# BLE_--_HM-10_--_Breakout_v_9_2.net
KiCad netlist of a schematic drawn in EAGLE
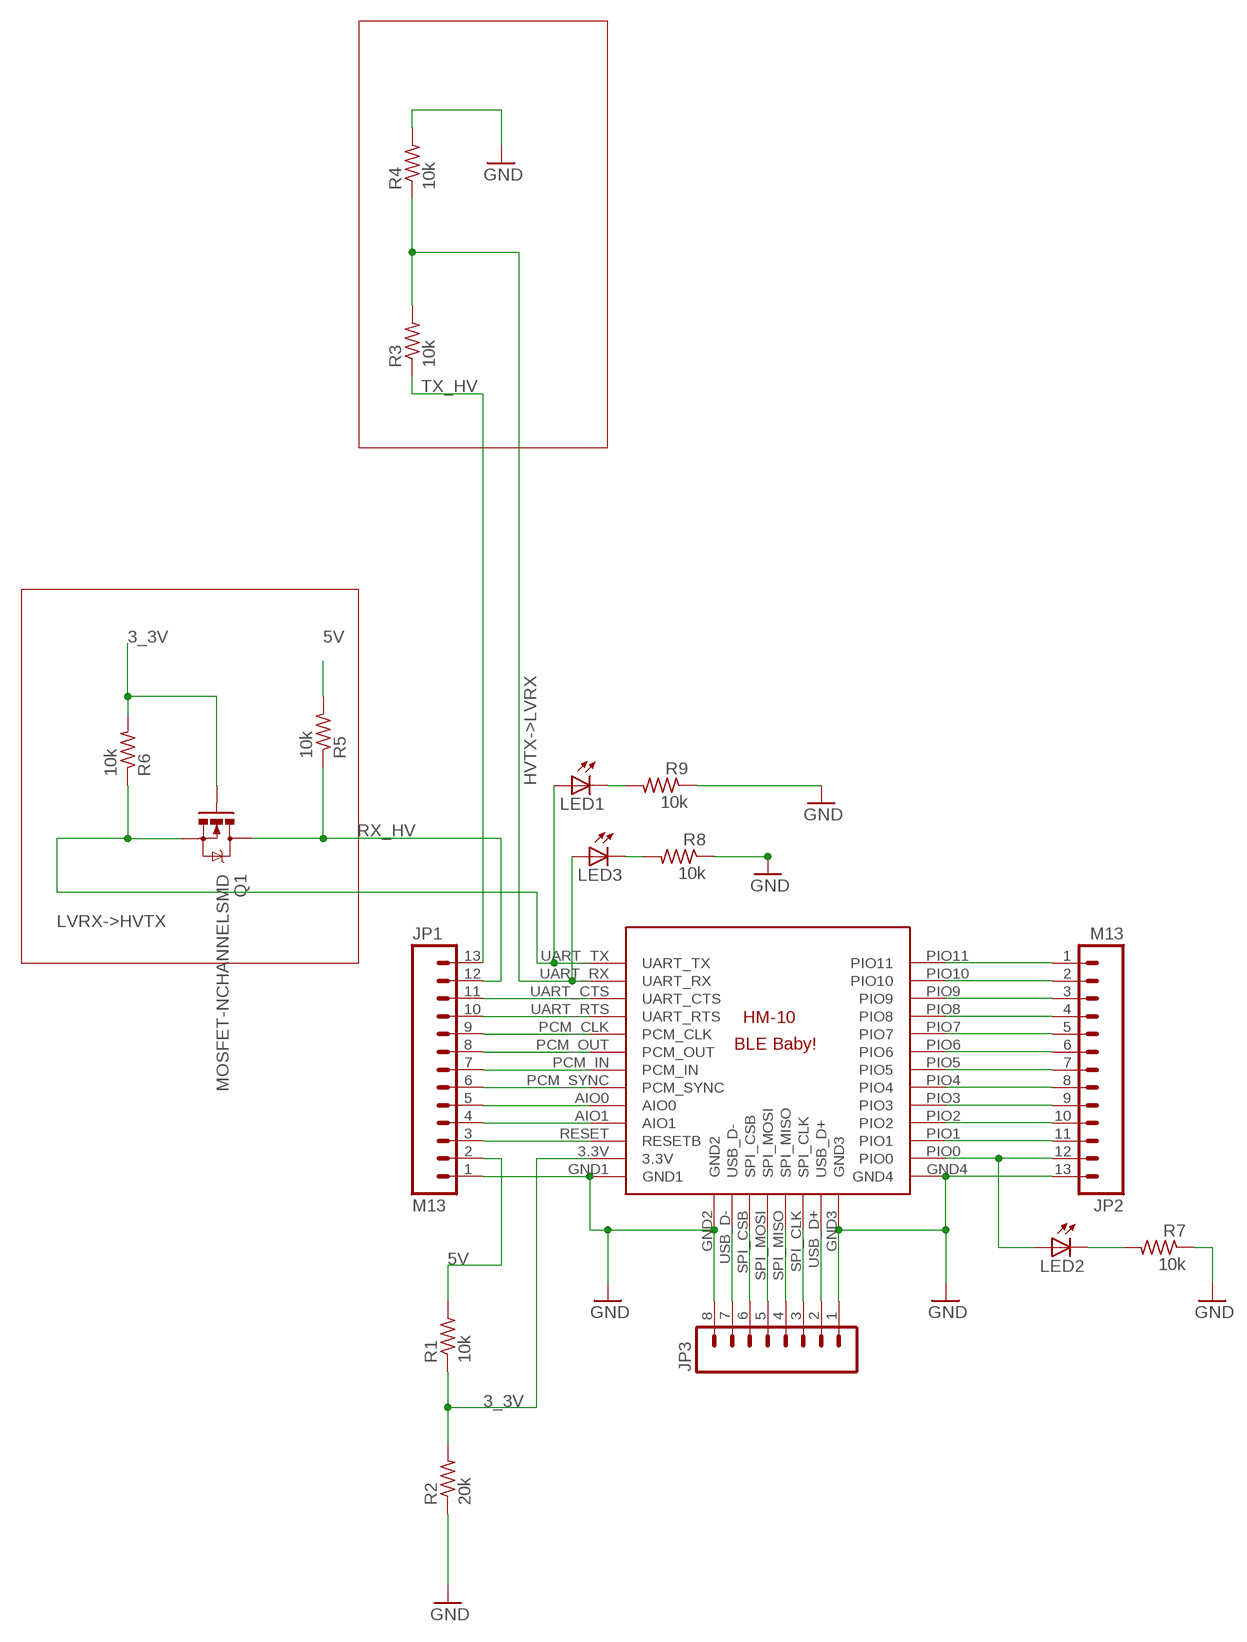
[diagram p0: schematic, sheet 1]

(export (version "E")
  (design (tool "Eeschema 10.0.6"))
  (components
    (comp (ref "JP1")
      (value "M13")
      (footprint "eagle-import:1X13")
      (libsource (lib "eagle-import") (part "M13"))
    )
    (comp (ref "JP2")
      (value "M13")
      (footprint "eagle-import:1X13")
      (libsource (lib "eagle-import") (part "M13"))
    )
    (comp (ref "JP3")
      (value "M081X08")
      (footprint "eagle-import:1X08")
      (libsource (lib "eagle-import") (part "M081X08"))
    )
    (comp (ref "LED1")
      (value "LED0603")
      (footprint "eagle-import:LED-0603")
      (libsource (lib "eagle-import") (part "LED0603"))
    )
    (comp (ref "LED2")
      (value "LED0603")
      (footprint "eagle-import:LED-0603")
      (libsource (lib "eagle-import") (part "LED0603"))
    )
    (comp (ref "LED3")
      (value "LED0603")
      (footprint "eagle-import:LED-0603")
      (libsource (lib "eagle-import") (part "LED0603"))
    )
    (comp (ref "Q1")
      (value "MOSFET-NCHANNELSMD")
      (footprint "eagle-import:SOT23-3")
      (libsource (lib "eagle-import") (part "MOSFET-NCHANNELSMD"))
    )
    (comp (ref "R1")
      (value "10k")
      (footprint "eagle-import:M0805")
      (libsource (lib "eagle-import") (part "R-US_M0805"))
    )
    (comp (ref "R2")
      (value "20k")
      (footprint "eagle-import:M0805")
      (libsource (lib "eagle-import") (part "R-US_M0805"))
    )
    (comp (ref "R3")
      (value "10k")
      (footprint "eagle-import:M0805")
      (libsource (lib "eagle-import") (part "R-US_M0805"))
    )
    (comp (ref "R4")
      (value "10k")
      (footprint "eagle-import:M0805")
      (libsource (lib "eagle-import") (part "R-US_M0805"))
    )
    (comp (ref "R5")
      (value "10k")
      (footprint "eagle-import:M0805")
      (libsource (lib "eagle-import") (part "R-US_M0805"))
    )
    (comp (ref "R6")
      (value "10k")
      (footprint "eagle-import:M0805")
      (libsource (lib "eagle-import") (part "R-US_M0805"))
    )
    (comp (ref "R7")
      (value "10k")
      (footprint "eagle-import:M0805")
      (libsource (lib "eagle-import") (part "R-US_M0805"))
    )
    (comp (ref "R8")
      (value "10k")
      (footprint "eagle-import:M0805")
      (libsource (lib "eagle-import") (part "R-US_M0805"))
    )
    (comp (ref "R9")
      (value "10k")
      (footprint "eagle-import:M0805")
      (libsource (lib "eagle-import") (part "R-US_M0805"))
    )
    (comp (ref "U$1")
      (value "BLE-HM-10")
      (footprint "eagle-import:BLE-HM-10")
      (libsource (lib "eagle-import") (part "BLE-HM-10"))
    )
  )
  (nets
    (net (code "1") (name "/3_3V") (class "Default")
      (node (ref "Q1") (pin "1") (pinfunction "G_1") (pintype "passive"))
      (node (ref "R1") (pin "1") (pinfunction "1_1") (pintype "passive"))
      (node (ref "R2") (pin "2") (pinfunction "2_2") (pintype "passive"))
      (node (ref "R6") (pin "2") (pinfunction "2_2") (pintype "passive"))
      (node (ref "U$1") (pin "3.3V") (pinfunction "3.3V_3.3V") (pintype "bidirectional"))
    )
    (net (code "2") (name "/5V") (class "Default")
      (node (ref "JP1") (pin "2") (pinfunction "2_2") (pintype "passive"))
      (node (ref "R1") (pin "2") (pinfunction "2_2") (pintype "passive"))
      (node (ref "R5") (pin "2") (pinfunction "2_2") (pintype "passive"))
    )
    (net (code "3") (name "/HVTX->LVRX") (class "Default")
      (node (ref "LED3") (pin "A") (pinfunction "A_A") (pintype "passive"))
      (node (ref "R3") (pin "2") (pinfunction "2_2") (pintype "passive"))
      (node (ref "R4") (pin "1") (pinfunction "1_1") (pintype "passive"))
      (node (ref "U$1") (pin "UART_RX") (pinfunction "UART_RX_UART_RX") (pintype "bidirectional"))
    )
    (net (code "4") (name "/LVRX->HVTX") (class "Default")
      (node (ref "LED1") (pin "A") (pinfunction "A_A") (pintype "passive"))
      (node (ref "Q1") (pin "2") (pinfunction "S_2") (pintype "passive"))
      (node (ref "R6") (pin "1") (pinfunction "1_1") (pintype "passive"))
      (node (ref "U$1") (pin "UART_TX") (pinfunction "UART_TX_UART_TX") (pintype "bidirectional"))
    )
    (net (code "5") (name "/RX_HV") (class "Default")
      (node (ref "JP1") (pin "12") (pinfunction "12_12") (pintype "passive"))
      (node (ref "Q1") (pin "3") (pinfunction "D_3") (pintype "passive"))
      (node (ref "R5") (pin "1") (pinfunction "1_1") (pintype "passive"))
    )
    (net (code "6") (name "/TX_HV") (class "Default")
      (node (ref "JP1") (pin "13") (pinfunction "13_13") (pintype "passive"))
      (node (ref "R3") (pin "1") (pinfunction "1_1") (pintype "passive"))
    )
    (net (code "7") (name "GND") (class "Default")
      (node (ref "JP1") (pin "1") (pinfunction "1_1") (pintype "passive"))
      (node (ref "JP2") (pin "13") (pinfunction "13_13") (pintype "passive"))
      (node (ref "JP3") (pin "1") (pinfunction "1_1") (pintype "passive"))
      (node (ref "JP3") (pin "8") (pinfunction "8_8") (pintype "passive"))
      (node (ref "R2") (pin "1") (pinfunction "1_1") (pintype "passive"))
      (node (ref "R4") (pin "2") (pinfunction "2_2") (pintype "passive"))
      (node (ref "R7") (pin "1") (pinfunction "1_1") (pintype "passive"))
      (node (ref "R8") (pin "1") (pinfunction "1_1") (pintype "passive"))
      (node (ref "R9") (pin "1") (pinfunction "1_1") (pintype "passive"))
      (node (ref "U$1") (pin "GND1") (pinfunction "GND1_GND1") (pintype "bidirectional"))
      (node (ref "U$1") (pin "GND2") (pinfunction "GND2_GND2") (pintype "bidirectional"))
      (node (ref "U$1") (pin "GND3") (pinfunction "GND3_GND3") (pintype "bidirectional"))
      (node (ref "U$1") (pin "GND4") (pinfunction "GND4_GND4") (pintype "bidirectional"))
    )
    (net (code "8") (name "Net-(JP1-Pad4)") (class "Default")
      (node (ref "JP1") (pin "4") (pinfunction "4_4") (pintype "passive"))
      (node (ref "U$1") (pin "AIO1") (pinfunction "AIO1_AIO1") (pintype "bidirectional"))
    )
    (net (code "9") (name "Net-(JP1-Pad5)") (class "Default")
      (node (ref "JP1") (pin "5") (pinfunction "5_5") (pintype "passive"))
      (node (ref "U$1") (pin "AIO0") (pinfunction "AIO0_AIO0") (pintype "bidirectional"))
    )
    (net (code "10") (name "Net-(JP1-Pad6)") (class "Default")
      (node (ref "JP1") (pin "6") (pinfunction "6_6") (pintype "passive"))
      (node (ref "U$1") (pin "PCM_SYNC") (pinfunction "PCM_SYNC_PCM_SYNC") (pintype "bidirectional"))
    )
    (net (code "11") (name "Net-(JP1-Pad7)") (class "Default")
      (node (ref "JP1") (pin "7") (pinfunction "7_7") (pintype "passive"))
      (node (ref "U$1") (pin "PCM_IN") (pinfunction "PCM_IN_PCM_IN") (pintype "bidirectional"))
    )
    (net (code "12") (name "Net-(JP1-Pad8)") (class "Default")
      (node (ref "JP1") (pin "8") (pinfunction "8_8") (pintype "passive"))
      (node (ref "U$1") (pin "PCM_OUT") (pinfunction "PCM_OUT_PCM_OUT") (pintype "bidirectional"))
    )
    (net (code "13") (name "Net-(JP1-Pad9)") (class "Default")
      (node (ref "JP1") (pin "9") (pinfunction "9_9") (pintype "passive"))
      (node (ref "U$1") (pin "PCM_CLK") (pinfunction "PCM_CLK_PCM_CLK") (pintype "bidirectional"))
    )
    (net (code "14") (name "Net-(JP1-Pad10)") (class "Default")
      (node (ref "JP1") (pin "10") (pinfunction "10_10") (pintype "passive"))
      (node (ref "U$1") (pin "UART_RTS") (pinfunction "UART_RTS_UART_RTS") (pintype "bidirectional"))
    )
    (net (code "15") (name "Net-(JP1-Pad11)") (class "Default")
      (node (ref "JP1") (pin "11") (pinfunction "11_11") (pintype "passive"))
      (node (ref "U$1") (pin "UART_CTS") (pinfunction "UART_CTS_UART_CTS") (pintype "bidirectional"))
    )
    (net (code "16") (name "Net-(JP2-Pad1)") (class "Default")
      (node (ref "JP2") (pin "1") (pinfunction "1_1") (pintype "passive"))
      (node (ref "U$1") (pin "PIO11") (pinfunction "PIO11_PIO11") (pintype "bidirectional"))
    )
    (net (code "17") (name "Net-(JP2-Pad2)") (class "Default")
      (node (ref "JP2") (pin "2") (pinfunction "2_2") (pintype "passive"))
      (node (ref "U$1") (pin "PIO10") (pinfunction "PIO10_PIO10") (pintype "bidirectional"))
    )
    (net (code "18") (name "Net-(JP2-Pad3)") (class "Default")
      (node (ref "JP2") (pin "3") (pinfunction "3_3") (pintype "passive"))
      (node (ref "U$1") (pin "PIO9") (pinfunction "PIO9_PIO9") (pintype "bidirectional"))
    )
    (net (code "19") (name "Net-(JP2-Pad4)") (class "Default")
      (node (ref "JP2") (pin "4") (pinfunction "4_4") (pintype "passive"))
      (node (ref "U$1") (pin "PIO8") (pinfunction "PIO8_PIO8") (pintype "bidirectional"))
    )
    (net (code "20") (name "Net-(JP2-Pad5)") (class "Default")
      (node (ref "JP2") (pin "5") (pinfunction "5_5") (pintype "passive"))
      (node (ref "U$1") (pin "PIO7") (pinfunction "PIO7_PIO7") (pintype "bidirectional"))
    )
    (net (code "21") (name "Net-(JP2-Pad6)") (class "Default")
      (node (ref "JP2") (pin "6") (pinfunction "6_6") (pintype "passive"))
      (node (ref "U$1") (pin "PIO6") (pinfunction "PIO6_PIO6") (pintype "bidirectional"))
    )
    (net (code "22") (name "Net-(JP2-Pad7)") (class "Default")
      (node (ref "JP2") (pin "7") (pinfunction "7_7") (pintype "passive"))
      (node (ref "U$1") (pin "PIO5") (pinfunction "PIO5_PIO5") (pintype "bidirectional"))
    )
    (net (code "23") (name "Net-(JP2-Pad8)") (class "Default")
      (node (ref "JP2") (pin "8") (pinfunction "8_8") (pintype "passive"))
      (node (ref "U$1") (pin "PIO4") (pinfunction "PIO4_PIO4") (pintype "bidirectional"))
    )
    (net (code "24") (name "Net-(JP2-Pad9)") (class "Default")
      (node (ref "JP2") (pin "9") (pinfunction "9_9") (pintype "passive"))
      (node (ref "U$1") (pin "PIO3") (pinfunction "PIO3_PIO3") (pintype "bidirectional"))
    )
    (net (code "25") (name "Net-(JP2-Pad10)") (class "Default")
      (node (ref "JP2") (pin "10") (pinfunction "10_10") (pintype "passive"))
      (node (ref "U$1") (pin "PIO2") (pinfunction "PIO2_PIO2") (pintype "bidirectional"))
    )
    (net (code "26") (name "Net-(JP2-Pad11)") (class "Default")
      (node (ref "JP2") (pin "11") (pinfunction "11_11") (pintype "passive"))
      (node (ref "U$1") (pin "PIO1") (pinfunction "PIO1_PIO1") (pintype "bidirectional"))
    )
    (net (code "27") (name "Net-(JP2-Pad12)") (class "Default")
      (node (ref "JP2") (pin "12") (pinfunction "12_12") (pintype "passive"))
      (node (ref "LED2") (pin "A") (pinfunction "A_A") (pintype "passive"))
      (node (ref "U$1") (pin "PIO0") (pinfunction "PIO0_PIO0") (pintype "bidirectional"))
    )
    (net (code "28") (name "Net-(JP3-Pad2)") (class "Default")
      (node (ref "JP3") (pin "2") (pinfunction "2_2") (pintype "passive"))
      (node (ref "U$1") (pin "USB_D+") (pinfunction "USB_D+_USB_D+") (pintype "bidirectional"))
    )
    (net (code "29") (name "Net-(JP3-Pad3)") (class "Default")
      (node (ref "JP3") (pin "3") (pinfunction "3_3") (pintype "passive"))
      (node (ref "U$1") (pin "SPI_CLK") (pinfunction "SPI_CLK_SPI_CLK") (pintype "bidirectional"))
    )
    (net (code "30") (name "Net-(JP3-Pad4)") (class "Default")
      (node (ref "JP3") (pin "4") (pinfunction "4_4") (pintype "passive"))
      (node (ref "U$1") (pin "SPI_MISO") (pinfunction "SPI_MISO_SPI_MISO") (pintype "bidirectional"))
    )
    (net (code "31") (name "Net-(JP3-Pad5)") (class "Default")
      (node (ref "JP3") (pin "5") (pinfunction "5_5") (pintype "passive"))
      (node (ref "U$1") (pin "SPI_MOSI") (pinfunction "SPI_MOSI_SPI_MOSI") (pintype "bidirectional"))
    )
    (net (code "32") (name "Net-(JP3-Pad6)") (class "Default")
      (node (ref "JP3") (pin "6") (pinfunction "6_6") (pintype "passive"))
      (node (ref "U$1") (pin "SPI_CSB") (pinfunction "SPI_CSB_SPI_CSB") (pintype "bidirectional"))
    )
    (net (code "33") (name "Net-(JP3-Pad7)") (class "Default")
      (node (ref "JP3") (pin "7") (pinfunction "7_7") (pintype "passive"))
      (node (ref "U$1") (pin "USB_D-") (pinfunction "USB_D-_USB_D-") (pintype "bidirectional"))
    )
    (net (code "34") (name "Net-(LED1-PadC)") (class "Default")
      (node (ref "LED1") (pin "C") (pinfunction "C_C") (pintype "passive"))
      (node (ref "R9") (pin "2") (pinfunction "2_2") (pintype "passive"))
    )
    (net (code "35") (name "Net-(LED2-PadC)") (class "Default")
      (node (ref "LED2") (pin "C") (pinfunction "C_C") (pintype "passive"))
      (node (ref "R7") (pin "2") (pinfunction "2_2") (pintype "passive"))
    )
    (net (code "36") (name "Net-(LED3-PadC)") (class "Default")
      (node (ref "LED3") (pin "C") (pinfunction "C_C") (pintype "passive"))
      (node (ref "R8") (pin "2") (pinfunction "2_2") (pintype "passive"))
    )
    (net (code "37") (name "Net-(U$1-RESETB)") (class "Default")
      (node (ref "JP1") (pin "3") (pinfunction "3_3") (pintype "passive"))
      (node (ref "U$1") (pin "RESET") (pinfunction "RESETB_RESET") (pintype "bidirectional"))
    )
  )
)
